# Filter.net
KiCad netlist of a schematic drawn in Altium Designer
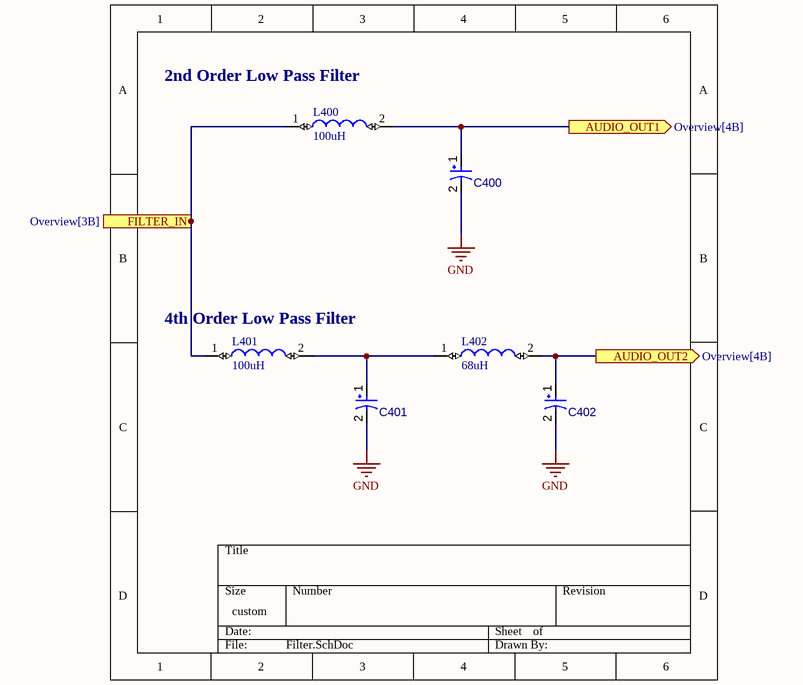
[diagram p0: Filter.SchDoc]

(export (version "E")
  (design (tool "Eeschema 10.0.6"))
  (components
    (comp (ref "C400")
      (value "630nF")
      (footprint "CAPPR65-500-1600X1000X1700")
      (fields (field (name "TOLERANCE") "20%") (field (name "MANUFACTURER") "Panasonic"))
      (libsource (lib "Rahulb 23") (part "CAP-P-2"))
    )
    (comp (ref "C401")
      (value "1.5uF")
      (footprint "CAPPR65-500-1600X1000X1700")
      (fields (field (name "TOLERANCE") "20%") (field (name "MANUFACTURER") "Panasonic"))
      (libsource (lib "Rahulb 23") (part "CAP-P-2"))
    )
    (comp (ref "C402")
      (value "390nF")
      (footprint "CAPPR65-500-1600X1000X1700")
      (fields (field (name "TOLERANCE") "20%") (field (name "MANUFACTURER") "Panasonic"))
      (libsource (lib "Rahulb 23") (part "CAP-P-2"))
    )
    (comp (ref "L400")
      (value "100uH")
      (footprint "SamacSys:RLB0914")
      (description "100uH Through Hole Inductor")
      (fields
        (field (name "MANUFACTURER_PART_NUMBER") "RLB0914-101KL")
        (field (name "MOUSER PART NUMBER") "652-RLB0914-101KL")
      )
      (libsource (lib "*") (part "RLB0914-101KL"))
    )
    (comp (ref "L401")
      (value "100uH")
      (footprint "SamacSys:RLB0914")
      (description "100uH Through Hole Inductor")
      (fields
        (field (name "MANUFACTURER_PART_NUMBER") "RLB0914-101KL")
        (field (name "MOUSER PART NUMBER") "652-RLB0914-101KL")
      )
      (libsource (lib "*") (part "RLB0914-101KL"))
    )
    (comp (ref "L402")
      (value "68uH")
      (footprint "SamacSys:RLB0914")
      (description "100uH Through Hole Inductor")
      (fields
        (field (name "MANUFACTURER_PART_NUMBER") "RLB0914-101KL")
        (field (name "MOUSER PART NUMBER") "652-RLB0914-101KL")
      )
      (libsource (lib "*") (part "RLB0914-101KL"))
    )
  )
  (nets
    (net (code "1") (name "/AUDIO_OUT1") (class "Default")
      (node (ref "C400") (pin "1") (pinfunction "1_1") (pintype "passive"))
      (node (ref "L400") (pin "2") (pinfunction "2_2") (pintype "bidirectional"))
    )
    (net (code "2") (name "/AUDIO_OUT2") (class "Default")
      (node (ref "C402") (pin "1") (pinfunction "1_1") (pintype "passive"))
      (node (ref "L402") (pin "2") (pinfunction "2_2") (pintype "bidirectional"))
    )
    (net (code "3") (name "/FILTER_IN") (class "Default")
      (node (ref "L400") (pin "1") (pinfunction "1_1") (pintype "bidirectional"))
      (node (ref "L401") (pin "1") (pinfunction "1_1") (pintype "bidirectional"))
    )
    (net (code "4") (name "GND") (class "Default")
      (node (ref "C400") (pin "2") (pinfunction "2_2") (pintype "passive"))
      (node (ref "C401") (pin "2") (pinfunction "2_2") (pintype "passive"))
      (node (ref "C402") (pin "2") (pinfunction "2_2") (pintype "passive"))
    )
    (net (code "5") (name "Net-(C401-Pad1)") (class "Default")
      (node (ref "C401") (pin "1") (pinfunction "1_1") (pintype "passive"))
      (node (ref "L401") (pin "2") (pinfunction "2_2") (pintype "bidirectional"))
      (node (ref "L402") (pin "1") (pinfunction "1_1") (pintype "bidirectional"))
    )
  )
)
